# 06_ZYNQ_PL.net
KiCad netlist of a schematic drawn in Altium Designer
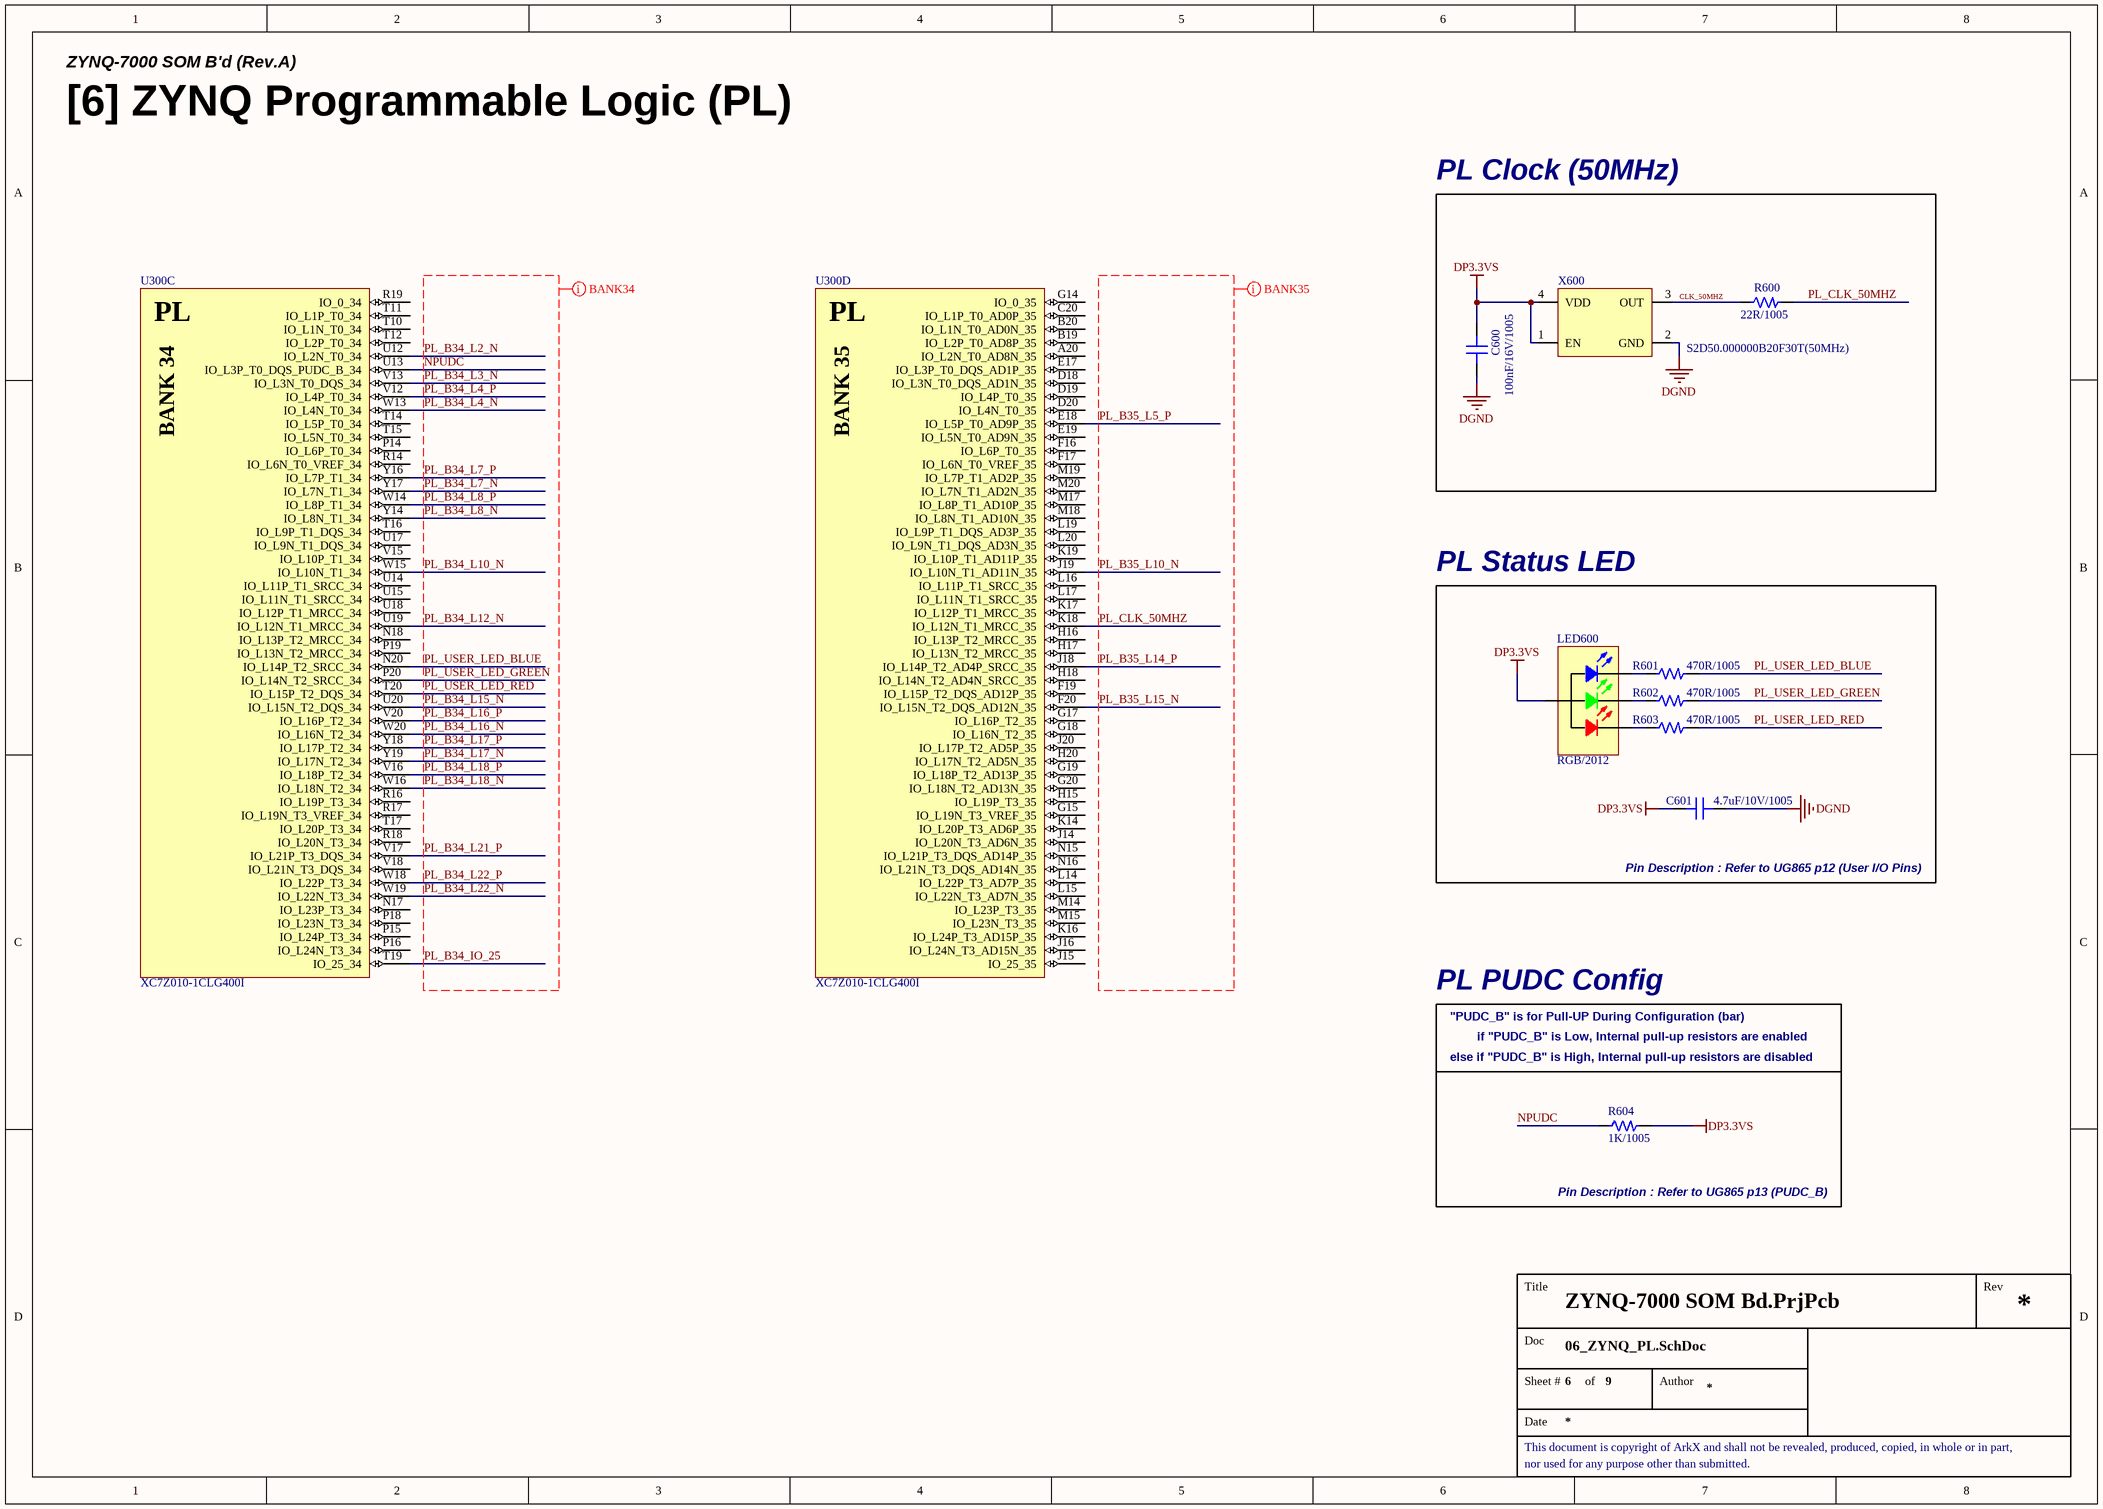
[diagram p0: 06_ZYNQ_PL.SchDoc]

(export (version "E")
  (design (tool "Eeschema 10.0.6"))
  (components
    (comp (ref "C600")
      (value "100nF/16V/1005")
      (footprint "CAP 1005 (0402_INCH)")
      (description "Ceramic CAP_100nF/16V/1005")
      (fields (field (name "LCSC PART #") "C1525"))
      (libsource (lib "Arkx") (part "CAP_100nF/16V/1005"))
    )
    (comp (ref "C601")
      (value "4.7uF/10V/1005")
      (footprint "CAP 1005 (0402_INCH)")
      (description "10V 4.7uF X5R ±20% 0402  Multilayer Ceramic Capacitors MLCC - SMD/SMT ROHS")
      (fields (field (name "LCSC PART #") "C23733"))
      (libsource (lib "Arkx") (part "CAP_4.7uF/10V/1005"))
    )
    (comp (ref "LED600")
      (value "RGB/2012")
      (footprint "LED MHT170RGBCT")
      (fields (field (name "LCSC PART #") "C2962094"))
      (libsource (lib "Arkx") (part "LED_RGB_MHT170RGBCT"))
    )
    (comp (ref "R600")
      (value "22R/1005")
      (footprint "RES 1005 (0402_inch)")
      (description "RES_22R/1005/62.5mW")
      (fields (field (name "LCSC PART #") "C25092"))
      (libsource (lib "Arkx") (part "RES_22R/1005/62.5mW"))
    )
    (comp (ref "R601")
      (value "470R/1005")
      (footprint "RES 1005 (0402_inch)")
      (description "RES_470R/1005/62.5mW")
      (fields (field (name "LCSC PART #") "C25117"))
      (libsource (lib "Arkx") (part "RES_470R/1005/62.5mW"))
    )
    (comp (ref "R602")
      (value "470R/1005")
      (footprint "RES 1005 (0402_inch)")
      (description "RES_470R/1005/62.5mW")
      (fields (field (name "LCSC PART #") "C25117"))
      (libsource (lib "Arkx") (part "RES_470R/1005/62.5mW"))
    )
    (comp (ref "R603")
      (value "470R/1005")
      (footprint "RES 1005 (0402_inch)")
      (description "RES_470R/1005/62.5mW")
      (fields (field (name "LCSC PART #") "C25117"))
      (libsource (lib "Arkx") (part "RES_470R/1005/62.5mW"))
    )
    (comp (ref "R604")
      (value "1K/1005")
      (footprint "RES 1005 (0402_inch)")
      (description "RES_1K/1005/62.5mW")
      (fields (field (name "LCSC PART #") "C11702"))
      (libsource (lib "Arkx") (part "RES_1K/1005/62.5mW"))
    )
    (comp (ref "U300")
      (value "XC7Z010-1CLG400I")
      (footprint "IC_SOC_XC7Z010-1CLG400I")
      (fields (field (name "LCSC PART #") "C2840994"))
      (libsource (lib "Arkx") (part "IC_SOC_XC7Z010-1CLG400I"))
    )
    (comp (ref "X600")
      (value "S2D50.000000B20F30T(50MHz)")
      (footprint "OSC SMD_2.5x2.0 (SCTF)")
      (description "3.3V 20mA ±30ppm CMOS 50MHz SMD2520-4P  Oscillators ROHS")
      (fields (field (name "LCSC PART #") "C907626"))
      (libsource (lib "Arkx") (part "OSC_S2D50.000000B20F30T(50MHz)"))
    )
  )
  (nets
    (net (code "1") (name "/CLK_50MHZ") (class "Default")
      (node (ref "R600") (pin "1") (pinfunction "1_1") (pintype "passive"))
      (node (ref "X600") (pin "3") (pinfunction "OUT_3") (pintype "passive"))
    )
    (net (code "2") (name "/NPUDC") (class "Default")
      (node (ref "R604") (pin "1") (pinfunction "1_1") (pintype "passive"))
      (node (ref "U300") (pin "U13") (pinfunction "IO_L3P_T0_DQS_PUDC_B_34_U13") (pintype "bidirectional"))
    )
    (net (code "3") (name "/PL_B34_IO_25") (class "Default")
      (node (ref "U300") (pin "T19") (pinfunction "IO_25_34_T19") (pintype "bidirectional"))
    )
    (net (code "4") (name "/PL_B34_L2_N") (class "Default")
      (node (ref "U300") (pin "U12") (pinfunction "IO_L2N_T0_34_U12") (pintype "bidirectional"))
    )
    (net (code "5") (name "/PL_B34_L3_N") (class "Default")
      (node (ref "U300") (pin "V13") (pinfunction "IO_L3N_T0_DQS_34_V13") (pintype "bidirectional"))
    )
    (net (code "6") (name "/PL_B34_L4_N") (class "Default")
      (node (ref "U300") (pin "W13") (pinfunction "IO_L4N_T0_34_W13") (pintype "bidirectional"))
    )
    (net (code "7") (name "/PL_B34_L4_P") (class "Default")
      (node (ref "U300") (pin "V12") (pinfunction "IO_L4P_T0_34_V12") (pintype "bidirectional"))
    )
    (net (code "8") (name "/PL_B34_L7_N") (class "Default")
      (node (ref "U300") (pin "Y17") (pinfunction "IO_L7N_T1_34_Y17") (pintype "bidirectional"))
    )
    (net (code "9") (name "/PL_B34_L7_P") (class "Default")
      (node (ref "U300") (pin "Y16") (pinfunction "IO_L7P_T1_34_Y16") (pintype "bidirectional"))
    )
    (net (code "10") (name "/PL_B34_L8_N") (class "Default")
      (node (ref "U300") (pin "Y14") (pinfunction "IO_L8N_T1_34_Y14") (pintype "bidirectional"))
    )
    (net (code "11") (name "/PL_B34_L8_P") (class "Default")
      (node (ref "U300") (pin "W14") (pinfunction "IO_L8P_T1_34_W14") (pintype "bidirectional"))
    )
    (net (code "12") (name "/PL_B34_L10_N") (class "Default")
      (node (ref "U300") (pin "W15") (pinfunction "IO_L10N_T1_34_W15") (pintype "bidirectional"))
    )
    (net (code "13") (name "/PL_B34_L12_N") (class "Default")
      (node (ref "U300") (pin "U19") (pinfunction "IO_L12N_T1_MRCC_34_U19") (pintype "bidirectional"))
    )
    (net (code "14") (name "/PL_B34_L15_N") (class "Default")
      (node (ref "U300") (pin "U20") (pinfunction "IO_L15N_T2_DQS_34_U20") (pintype "bidirectional"))
    )
    (net (code "15") (name "/PL_B34_L16_N") (class "Default")
      (node (ref "U300") (pin "W20") (pinfunction "IO_L16N_T2_34_W20") (pintype "bidirectional"))
    )
    (net (code "16") (name "/PL_B34_L16_P") (class "Default")
      (node (ref "U300") (pin "V20") (pinfunction "IO_L16P_T2_34_V20") (pintype "bidirectional"))
    )
    (net (code "17") (name "/PL_B34_L17_N") (class "Default")
      (node (ref "U300") (pin "Y19") (pinfunction "IO_L17N_T2_34_Y19") (pintype "bidirectional"))
    )
    (net (code "18") (name "/PL_B34_L17_P") (class "Default")
      (node (ref "U300") (pin "Y18") (pinfunction "IO_L17P_T2_34_Y18") (pintype "bidirectional"))
    )
    (net (code "19") (name "/PL_B34_L18_N") (class "Default")
      (node (ref "U300") (pin "W16") (pinfunction "IO_L18N_T2_34_W16") (pintype "bidirectional"))
    )
    (net (code "20") (name "/PL_B34_L18_P") (class "Default")
      (node (ref "U300") (pin "V16") (pinfunction "IO_L18P_T2_34_V16") (pintype "bidirectional"))
    )
    (net (code "21") (name "/PL_B34_L21_P") (class "Default")
      (node (ref "U300") (pin "V17") (pinfunction "IO_L21P_T3_DQS_34_V17") (pintype "bidirectional"))
    )
    (net (code "22") (name "/PL_B34_L22_N") (class "Default")
      (node (ref "U300") (pin "W19") (pinfunction "IO_L22N_T3_34_W19") (pintype "bidirectional"))
    )
    (net (code "23") (name "/PL_B34_L22_P") (class "Default")
      (node (ref "U300") (pin "W18") (pinfunction "IO_L22P_T3_34_W18") (pintype "bidirectional"))
    )
    (net (code "24") (name "/PL_B35_L5_P") (class "Default")
      (node (ref "U300") (pin "E18") (pinfunction "IO_L5P_T0_AD9P_35_E18") (pintype "bidirectional"))
    )
    (net (code "25") (name "/PL_B35_L10_N") (class "Default")
      (node (ref "U300") (pin "J19") (pinfunction "IO_L10N_T1_AD11N_35_J19") (pintype "bidirectional"))
    )
    (net (code "26") (name "/PL_B35_L14_P") (class "Default")
      (node (ref "U300") (pin "J18") (pinfunction "IO_L14P_T2_AD4P_SRCC_35_J18") (pintype "bidirectional"))
    )
    (net (code "27") (name "/PL_B35_L15_N") (class "Default")
      (node (ref "U300") (pin "F20") (pinfunction "IO_L15N_T2_DQS_AD12N_35_F20") (pintype "bidirectional"))
    )
    (net (code "28") (name "/PL_CLK_50MHZ") (class "Default")
      (node (ref "R600") (pin "2") (pinfunction "2_2") (pintype "passive"))
      (node (ref "U300") (pin "K18") (pinfunction "IO_L12N_T1_MRCC_35_K18") (pintype "bidirectional"))
    )
    (net (code "29") (name "/PL_USER_LED_BLUE") (class "Default")
      (node (ref "R601") (pin "2") (pinfunction "2_2") (pintype "passive"))
      (node (ref "U300") (pin "N20") (pinfunction "IO_L14P_T2_SRCC_34_N20") (pintype "bidirectional"))
    )
    (net (code "30") (name "/PL_USER_LED_GREEN") (class "Default")
      (node (ref "R602") (pin "2") (pinfunction "2_2") (pintype "passive"))
      (node (ref "U300") (pin "P20") (pinfunction "IO_L14N_T2_SRCC_34_P20") (pintype "bidirectional"))
    )
    (net (code "31") (name "/PL_USER_LED_RED") (class "Default")
      (node (ref "R603") (pin "2") (pinfunction "2_2") (pintype "passive"))
      (node (ref "U300") (pin "T20") (pinfunction "IO_L15P_T2_DQS_34_T20") (pintype "bidirectional"))
    )
    (net (code "32") (name "DGND") (class "Default")
      (node (ref "C600") (pin "2") (pinfunction "2_2") (pintype "passive"))
      (node (ref "C601") (pin "1") (pinfunction "1_1") (pintype "passive"))
      (node (ref "X600") (pin "2") (pinfunction "GND_2") (pintype "passive"))
    )
    (net (code "33") (name "DP3.3VS") (class "Default")
      (node (ref "C600") (pin "1") (pinfunction "1_1") (pintype "passive"))
      (node (ref "C601") (pin "2") (pinfunction "2_2") (pintype "passive"))
      (node (ref "LED600") (pin "4") (pinfunction "Common_Anode_4") (pintype "passive"))
      (node (ref "R604") (pin "2") (pinfunction "2_2") (pintype "passive"))
      (node (ref "X600") (pin "1") (pinfunction "EN_1") (pintype "passive"))
      (node (ref "X600") (pin "4") (pinfunction "VDD_4") (pintype "passive"))
    )
    (net (code "34") (name "Net-(LED600-BLUE)") (class "Default")
      (node (ref "LED600") (pin "3") (pinfunction "BLUE_3") (pintype "passive"))
      (node (ref "R601") (pin "1") (pinfunction "1_1") (pintype "passive"))
    )
    (net (code "35") (name "Net-(LED600-GREEN)") (class "Default")
      (node (ref "LED600") (pin "2") (pinfunction "GREEN_2") (pintype "passive"))
      (node (ref "R602") (pin "1") (pinfunction "1_1") (pintype "passive"))
    )
    (net (code "36") (name "Net-(LED600-RED)") (class "Default")
      (node (ref "LED600") (pin "1") (pinfunction "RED_1") (pintype "passive"))
      (node (ref "R603") (pin "1") (pinfunction "1_1") (pintype "passive"))
    )
    (net (code "37") (name "unconnected-(U300C-IO_0_34-PadR19)") (class "Default")
      (node (ref "U300") (pin "R19") (pinfunction "IO_0_34_R19") (pintype "bidirectional"))
    )
    (net (code "38") (name "unconnected-(U300C-IO_L1N_T0_34-PadT10)") (class "Default")
      (node (ref "U300") (pin "T10") (pinfunction "IO_L1N_T0_34_T10") (pintype "bidirectional"))
    )
    (net (code "39") (name "unconnected-(U300C-IO_L1P_T0_34-PadT11)") (class "Default")
      (node (ref "U300") (pin "T11") (pinfunction "IO_L1P_T0_34_T11") (pintype "bidirectional"))
    )
    (net (code "40") (name "unconnected-(U300C-IO_L2P_T0_34-PadT12)") (class "Default")
      (node (ref "U300") (pin "T12") (pinfunction "IO_L2P_T0_34_T12") (pintype "bidirectional"))
    )
    (net (code "41") (name "unconnected-(U300C-IO_L5N_T0_34-PadT15)") (class "Default")
      (node (ref "U300") (pin "T15") (pinfunction "IO_L5N_T0_34_T15") (pintype "bidirectional"))
    )
    (net (code "42") (name "unconnected-(U300C-IO_L5P_T0_34-PadT14)") (class "Default")
      (node (ref "U300") (pin "T14") (pinfunction "IO_L5P_T0_34_T14") (pintype "bidirectional"))
    )
    (net (code "43") (name "unconnected-(U300C-IO_L6N_T0_VREF_34-PadR14)") (class "Default")
      (node (ref "U300") (pin "R14") (pinfunction "IO_L6N_T0_VREF_34_R14") (pintype "bidirectional"))
    )
    (net (code "44") (name "unconnected-(U300C-IO_L6P_T0_34-PadP14)") (class "Default")
      (node (ref "U300") (pin "P14") (pinfunction "IO_L6P_T0_34_P14") (pintype "bidirectional"))
    )
    (net (code "45") (name "unconnected-(U300C-IO_L9N_T1_DQS_34-PadU17)") (class "Default")
      (node (ref "U300") (pin "U17") (pinfunction "IO_L9N_T1_DQS_34_U17") (pintype "bidirectional"))
    )
    (net (code "46") (name "unconnected-(U300C-IO_L9P_T1_DQS_34-PadT16)") (class "Default")
      (node (ref "U300") (pin "T16") (pinfunction "IO_L9P_T1_DQS_34_T16") (pintype "bidirectional"))
    )
    (net (code "47") (name "unconnected-(U300C-IO_L10P_T1_34-PadV15)") (class "Default")
      (node (ref "U300") (pin "V15") (pinfunction "IO_L10P_T1_34_V15") (pintype "bidirectional"))
    )
    (net (code "48") (name "unconnected-(U300C-IO_L11N_T1_SRCC_34-PadU15)") (class "Default")
      (node (ref "U300") (pin "U15") (pinfunction "IO_L11N_T1_SRCC_34_U15") (pintype "bidirectional"))
    )
    (net (code "49") (name "unconnected-(U300C-IO_L11P_T1_SRCC_34-PadU14)") (class "Default")
      (node (ref "U300") (pin "U14") (pinfunction "IO_L11P_T1_SRCC_34_U14") (pintype "bidirectional"))
    )
    (net (code "50") (name "unconnected-(U300C-IO_L12P_T1_MRCC_34-PadU18)") (class "Default")
      (node (ref "U300") (pin "U18") (pinfunction "IO_L12P_T1_MRCC_34_U18") (pintype "bidirectional"))
    )
    (net (code "51") (name "unconnected-(U300C-IO_L13N_T2_MRCC_34-PadP19)") (class "Default")
      (node (ref "U300") (pin "P19") (pinfunction "IO_L13N_T2_MRCC_34_P19") (pintype "bidirectional"))
    )
    (net (code "52") (name "unconnected-(U300C-IO_L13P_T2_MRCC_34-PadN18)") (class "Default")
      (node (ref "U300") (pin "N18") (pinfunction "IO_L13P_T2_MRCC_34_N18") (pintype "bidirectional"))
    )
    (net (code "53") (name "unconnected-(U300C-IO_L19N_T3_VREF_34-PadR17)") (class "Default")
      (node (ref "U300") (pin "R17") (pinfunction "IO_L19N_T3_VREF_34_R17") (pintype "bidirectional"))
    )
    (net (code "54") (name "unconnected-(U300C-IO_L19P_T3_34-PadR16)") (class "Default")
      (node (ref "U300") (pin "R16") (pinfunction "IO_L19P_T3_34_R16") (pintype "bidirectional"))
    )
    (net (code "55") (name "unconnected-(U300C-IO_L20N_T3_34-PadR18)") (class "Default")
      (node (ref "U300") (pin "R18") (pinfunction "IO_L20N_T3_34_R18") (pintype "bidirectional"))
    )
    (net (code "56") (name "unconnected-(U300C-IO_L20P_T3_34-PadT17)") (class "Default")
      (node (ref "U300") (pin "T17") (pinfunction "IO_L20P_T3_34_T17") (pintype "bidirectional"))
    )
    (net (code "57") (name "unconnected-(U300C-IO_L21N_T3_DQS_34-PadV18)") (class "Default")
      (node (ref "U300") (pin "V18") (pinfunction "IO_L21N_T3_DQS_34_V18") (pintype "bidirectional"))
    )
    (net (code "58") (name "unconnected-(U300C-IO_L23N_T3_34-PadP18)") (class "Default")
      (node (ref "U300") (pin "P18") (pinfunction "IO_L23N_T3_34_P18") (pintype "bidirectional"))
    )
    (net (code "59") (name "unconnected-(U300C-IO_L23P_T3_34-PadN17)") (class "Default")
      (node (ref "U300") (pin "N17") (pinfunction "IO_L23P_T3_34_N17") (pintype "bidirectional"))
    )
    (net (code "60") (name "unconnected-(U300C-IO_L24N_T3_34-PadP16)") (class "Default")
      (node (ref "U300") (pin "P16") (pinfunction "IO_L24N_T3_34_P16") (pintype "bidirectional"))
    )
    (net (code "61") (name "unconnected-(U300C-IO_L24P_T3_34-PadP15)") (class "Default")
      (node (ref "U300") (pin "P15") (pinfunction "IO_L24P_T3_34_P15") (pintype "bidirectional"))
    )
    (net (code "62") (name "unconnected-(U300D-IO_0_35-PadG14)") (class "Default")
      (node (ref "U300") (pin "G14") (pinfunction "IO_0_35_G14") (pintype "bidirectional"))
    )
    (net (code "63") (name "unconnected-(U300D-IO_25_35-PadJ15)") (class "Default")
      (node (ref "U300") (pin "J15") (pinfunction "IO_25_35_J15") (pintype "bidirectional"))
    )
    (net (code "64") (name "unconnected-(U300D-IO_L1N_T0_AD0N_35-PadB20)") (class "Default")
      (node (ref "U300") (pin "B20") (pinfunction "IO_L1N_T0_AD0N_35_B20") (pintype "bidirectional"))
    )
    (net (code "65") (name "unconnected-(U300D-IO_L1P_T0_AD0P_35-PadC20)") (class "Default")
      (node (ref "U300") (pin "C20") (pinfunction "IO_L1P_T0_AD0P_35_C20") (pintype "bidirectional"))
    )
    (net (code "66") (name "unconnected-(U300D-IO_L2N_T0_AD8N_35-PadA20)") (class "Default")
      (node (ref "U300") (pin "A20") (pinfunction "IO_L2N_T0_AD8N_35_A20") (pintype "bidirectional"))
    )
    (net (code "67") (name "unconnected-(U300D-IO_L2P_T0_AD8P_35-PadB19)") (class "Default")
      (node (ref "U300") (pin "B19") (pinfunction "IO_L2P_T0_AD8P_35_B19") (pintype "bidirectional"))
    )
    (net (code "68") (name "unconnected-(U300D-IO_L3N_T0_DQS_AD1N_35-PadD18)") (class "Default")
      (node (ref "U300") (pin "D18") (pinfunction "IO_L3N_T0_DQS_AD1N_35_D18") (pintype "bidirectional"))
    )
    (net (code "69") (name "unconnected-(U300D-IO_L3P_T0_DQS_AD1P_35-PadE17)") (class "Default")
      (node (ref "U300") (pin "E17") (pinfunction "IO_L3P_T0_DQS_AD1P_35_E17") (pintype "bidirectional"))
    )
    (net (code "70") (name "unconnected-(U300D-IO_L4N_T0_35-PadD20)") (class "Default")
      (node (ref "U300") (pin "D20") (pinfunction "IO_L4N_T0_35_D20") (pintype "bidirectional"))
    )
    (net (code "71") (name "unconnected-(U300D-IO_L4P_T0_35-PadD19)") (class "Default")
      (node (ref "U300") (pin "D19") (pinfunction "IO_L4P_T0_35_D19") (pintype "bidirectional"))
    )
    (net (code "72") (name "unconnected-(U300D-IO_L5N_T0_AD9N_35-PadE19)") (class "Default")
      (node (ref "U300") (pin "E19") (pinfunction "IO_L5N_T0_AD9N_35_E19") (pintype "bidirectional"))
    )
    (net (code "73") (name "unconnected-(U300D-IO_L6N_T0_VREF_35-PadF17)") (class "Default")
      (node (ref "U300") (pin "F17") (pinfunction "IO_L6N_T0_VREF_35_F17") (pintype "bidirectional"))
    )
    (net (code "74") (name "unconnected-(U300D-IO_L6P_T0_35-PadF16)") (class "Default")
      (node (ref "U300") (pin "F16") (pinfunction "IO_L6P_T0_35_F16") (pintype "bidirectional"))
    )
    (net (code "75") (name "unconnected-(U300D-IO_L7N_T1_AD2N_35-PadM20)") (class "Default")
      (node (ref "U300") (pin "M20") (pinfunction "IO_L7N_T1_AD2N_35_M20") (pintype "bidirectional"))
    )
    (net (code "76") (name "unconnected-(U300D-IO_L7P_T1_AD2P_35-PadM19)") (class "Default")
      (node (ref "U300") (pin "M19") (pinfunction "IO_L7P_T1_AD2P_35_M19") (pintype "bidirectional"))
    )
    (net (code "77") (name "unconnected-(U300D-IO_L8N_T1_AD10N_35-PadM18)") (class "Default")
      (node (ref "U300") (pin "M18") (pinfunction "IO_L8N_T1_AD10N_35_M18") (pintype "bidirectional"))
    )
    (net (code "78") (name "unconnected-(U300D-IO_L8P_T1_AD10P_35-PadM17)") (class "Default")
      (node (ref "U300") (pin "M17") (pinfunction "IO_L8P_T1_AD10P_35_M17") (pintype "bidirectional"))
    )
    (net (code "79") (name "unconnected-(U300D-IO_L9N_T1_DQS_AD3N_35-PadL20)") (class "Default")
      (node (ref "U300") (pin "L20") (pinfunction "IO_L9N_T1_DQS_AD3N_35_L20") (pintype "bidirectional"))
    )
    (net (code "80") (name "unconnected-(U300D-IO_L9P_T1_DQS_AD3P_35-PadL19)") (class "Default")
      (node (ref "U300") (pin "L19") (pinfunction "IO_L9P_T1_DQS_AD3P_35_L19") (pintype "bidirectional"))
    )
    (net (code "81") (name "unconnected-(U300D-IO_L10P_T1_AD11P_35-PadK19)") (class "Default")
      (node (ref "U300") (pin "K19") (pinfunction "IO_L10P_T1_AD11P_35_K19") (pintype "bidirectional"))
    )
    (net (code "82") (name "unconnected-(U300D-IO_L11N_T1_SRCC_35-PadL17)") (class "Default")
      (node (ref "U300") (pin "L17") (pinfunction "IO_L11N_T1_SRCC_35_L17") (pintype "bidirectional"))
    )
    (net (code "83") (name "unconnected-(U300D-IO_L11P_T1_SRCC_35-PadL16)") (class "Default")
      (node (ref "U300") (pin "L16") (pinfunction "IO_L11P_T1_SRCC_35_L16") (pintype "bidirectional"))
    )
    (net (code "84") (name "unconnected-(U300D-IO_L12P_T1_MRCC_35-PadK17)") (class "Default")
      (node (ref "U300") (pin "K17") (pinfunction "IO_L12P_T1_MRCC_35_K17") (pintype "bidirectional"))
    )
    (net (code "85") (name "unconnected-(U300D-IO_L13N_T2_MRCC_35-PadH17)") (class "Default")
      (node (ref "U300") (pin "H17") (pinfunction "IO_L13N_T2_MRCC_35_H17") (pintype "bidirectional"))
    )
    (net (code "86") (name "unconnected-(U300D-IO_L13P_T2_MRCC_35-PadH16)") (class "Default")
      (node (ref "U300") (pin "H16") (pinfunction "IO_L13P_T2_MRCC_35_H16") (pintype "bidirectional"))
    )
    (net (code "87") (name "unconnected-(U300D-IO_L14N_T2_AD4N_SRCC_35-PadH18)") (class "Default")
      (node (ref "U300") (pin "H18") (pinfunction "IO_L14N_T2_AD4N_SRCC_35_H18") (pintype "bidirectional"))
    )
    (net (code "88") (name "unconnected-(U300D-IO_L15P_T2_DQS_AD12P_35-PadF19)") (class "Default")
      (node (ref "U300") (pin "F19") (pinfunction "IO_L15P_T2_DQS_AD12P_35_F19") (pintype "bidirectional"))
    )
    (net (code "89") (name "unconnected-(U300D-IO_L16N_T2_35-PadG18)") (class "Default")
      (node (ref "U300") (pin "G18") (pinfunction "IO_L16N_T2_35_G18") (pintype "bidirectional"))
    )
    (net (code "90") (name "unconnected-(U300D-IO_L16P_T2_35-PadG17)") (class "Default")
      (node (ref "U300") (pin "G17") (pinfunction "IO_L16P_T2_35_G17") (pintype "bidirectional"))
    )
    (net (code "91") (name "unconnected-(U300D-IO_L17N_T2_AD5N_35-PadH20)") (class "Default")
      (node (ref "U300") (pin "H20") (pinfunction "IO_L17N_T2_AD5N_35_H20") (pintype "bidirectional"))
    )
    (net (code "92") (name "unconnected-(U300D-IO_L17P_T2_AD5P_35-PadJ20)") (class "Default")
      (node (ref "U300") (pin "J20") (pinfunction "IO_L17P_T2_AD5P_35_J20") (pintype "bidirectional"))
    )
    (net (code "93") (name "unconnected-(U300D-IO_L18N_T2_AD13N_35-PadG20)") (class "Default")
      (node (ref "U300") (pin "G20") (pinfunction "IO_L18N_T2_AD13N_35_G20") (pintype "bidirectional"))
    )
    (net (code "94") (name "unconnected-(U300D-IO_L18P_T2_AD13P_35-PadG19)") (class "Default")
      (node (ref "U300") (pin "G19") (pinfunction "IO_L18P_T2_AD13P_35_G19") (pintype "bidirectional"))
    )
    (net (code "95") (name "unconnected-(U300D-IO_L19N_T3_VREF_35-PadG15)") (class "Default")
      (node (ref "U300") (pin "G15") (pinfunction "IO_L19N_T3_VREF_35_G15") (pintype "bidirectional"))
    )
    (net (code "96") (name "unconnected-(U300D-IO_L19P_T3_35-PadH15)") (class "Default")
      (node (ref "U300") (pin "H15") (pinfunction "IO_L19P_T3_35_H15") (pintype "bidirectional"))
    )
    (net (code "97") (name "unconnected-(U300D-IO_L20N_T3_AD6N_35-PadJ14)") (class "Default")
      (node (ref "U300") (pin "J14") (pinfunction "IO_L20N_T3_AD6N_35_J14") (pintype "bidirectional"))
    )
    (net (code "98") (name "unconnected-(U300D-IO_L20P_T3_AD6P_35-PadK14)") (class "Default")
      (node (ref "U300") (pin "K14") (pinfunction "IO_L20P_T3_AD6P_35_K14") (pintype "bidirectional"))
    )
    (net (code "99") (name "unconnected-(U300D-IO_L21N_T3_DQS_AD14N_35-PadN16)") (class "Default")
      (node (ref "U300") (pin "N16") (pinfunction "IO_L21N_T3_DQS_AD14N_35_N16") (pintype "bidirectional"))
    )
    (net (code "100") (name "unconnected-(U300D-IO_L21P_T3_DQS_AD14P_35-PadN15)") (class "Default")
      (node (ref "U300") (pin "N15") (pinfunction "IO_L21P_T3_DQS_AD14P_35_N15") (pintype "bidirectional"))
    )
    (net (code "101") (name "unconnected-(U300D-IO_L22N_T3_AD7N_35-PadL15)") (class "Default")
      (node (ref "U300") (pin "L15") (pinfunction "IO_L22N_T3_AD7N_35_L15") (pintype "bidirectional"))
    )
    (net (code "102") (name "unconnected-(U300D-IO_L22P_T3_AD7P_35-PadL14)") (class "Default")
      (node (ref "U300") (pin "L14") (pinfunction "IO_L22P_T3_AD7P_35_L14") (pintype "bidirectional"))
    )
    (net (code "103") (name "unconnected-(U300D-IO_L23N_T3_35-PadM15)") (class "Default")
      (node (ref "U300") (pin "M15") (pinfunction "IO_L23N_T3_35_M15") (pintype "bidirectional"))
    )
    (net (code "104") (name "unconnected-(U300D-IO_L23P_T3_35-PadM14)") (class "Default")
      (node (ref "U300") (pin "M14") (pinfunction "IO_L23P_T3_35_M14") (pintype "bidirectional"))
    )
    (net (code "105") (name "unconnected-(U300D-IO_L24N_T3_AD15N_35-PadJ16)") (class "Default")
      (node (ref "U300") (pin "J16") (pinfunction "IO_L24N_T3_AD15N_35_J16") (pintype "bidirectional"))
    )
    (net (code "106") (name "unconnected-(U300D-IO_L24P_T3_AD15P_35-PadK16)") (class "Default")
      (node (ref "U300") (pin "K16") (pinfunction "IO_L24P_T3_AD15P_35_K16") (pintype "bidirectional"))
    )
  )
)
